# top.net
KiCad netlist of a schematic drawn in Altium Designer
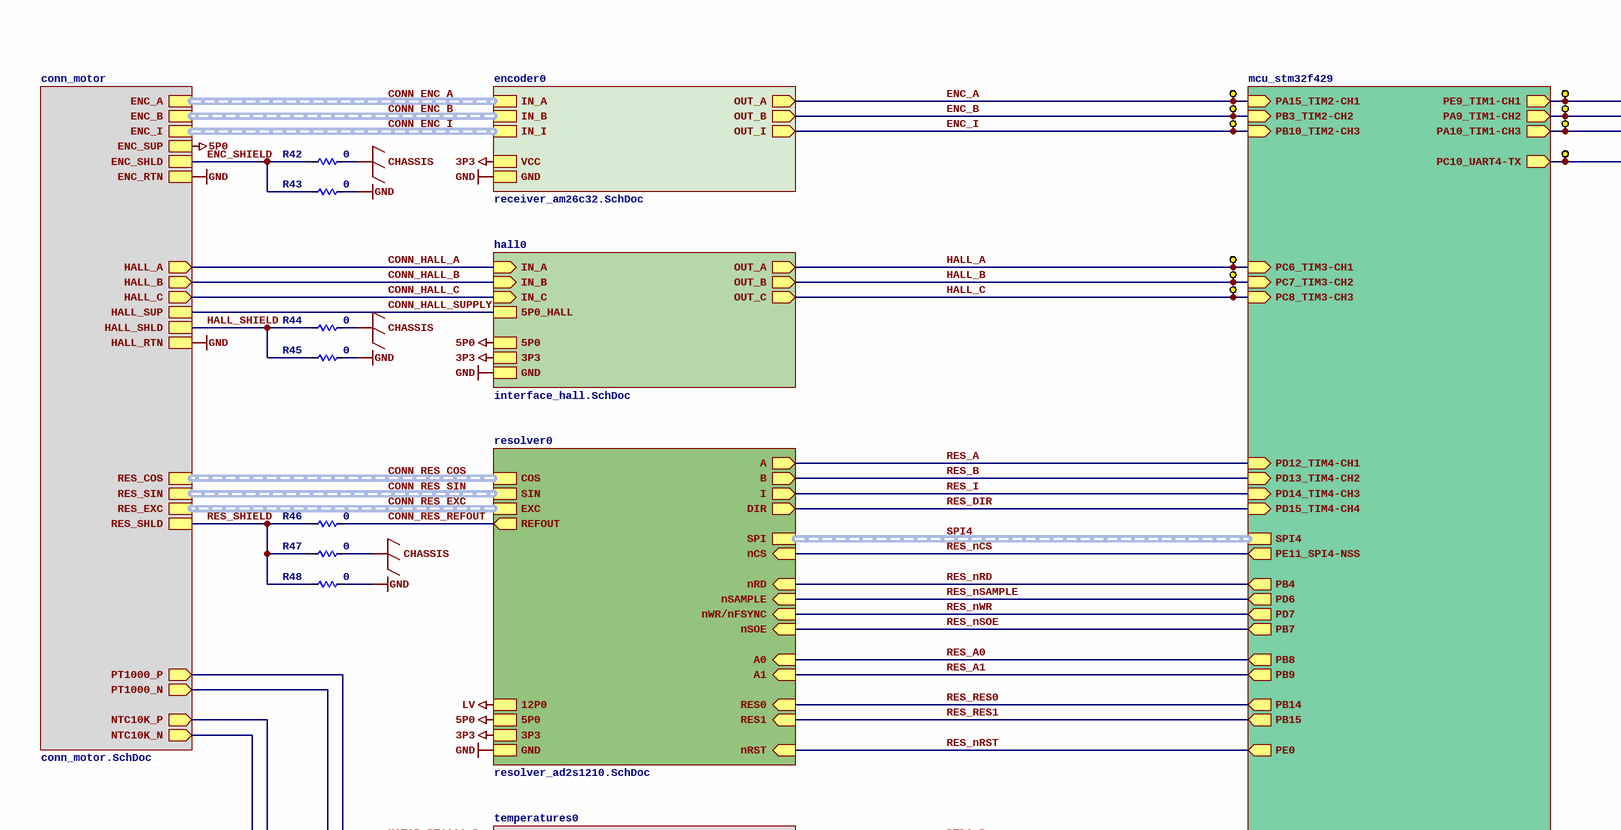
[diagram p0: top.SchDoc, top left]
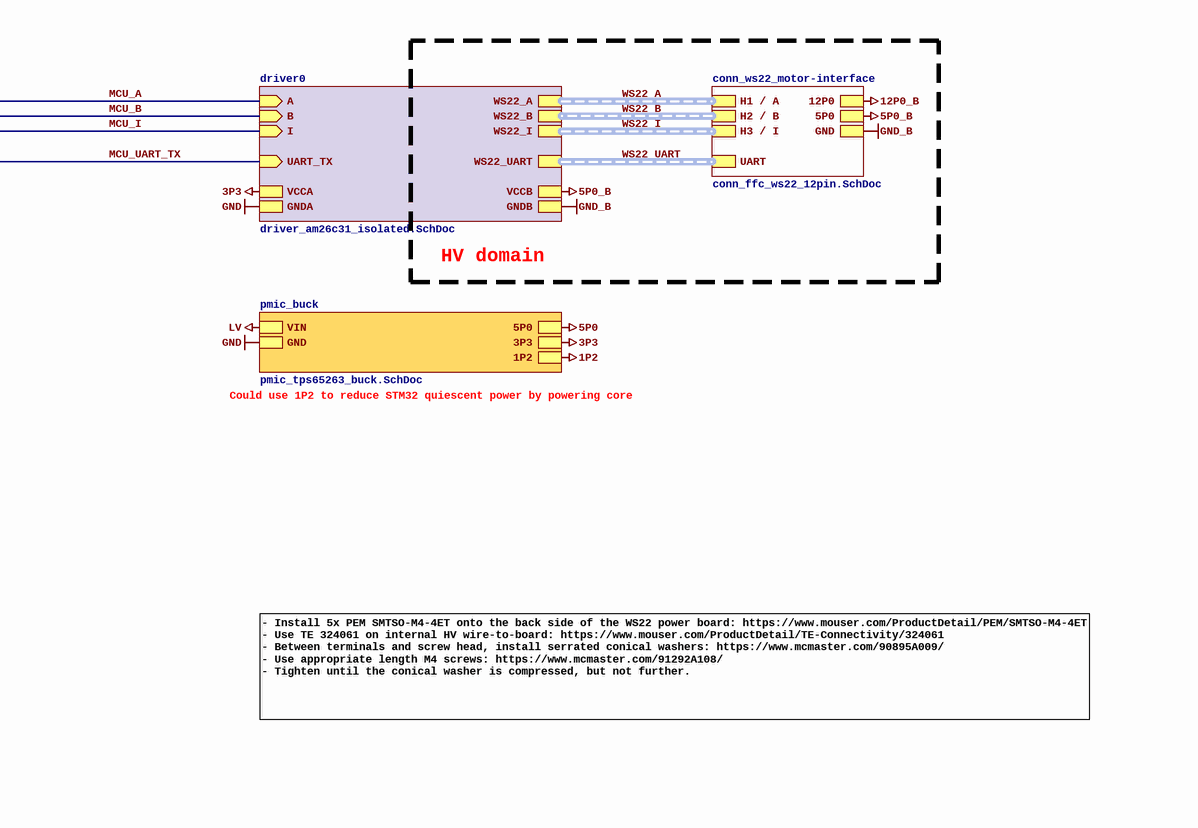
[diagram p1: top.SchDoc, top right]
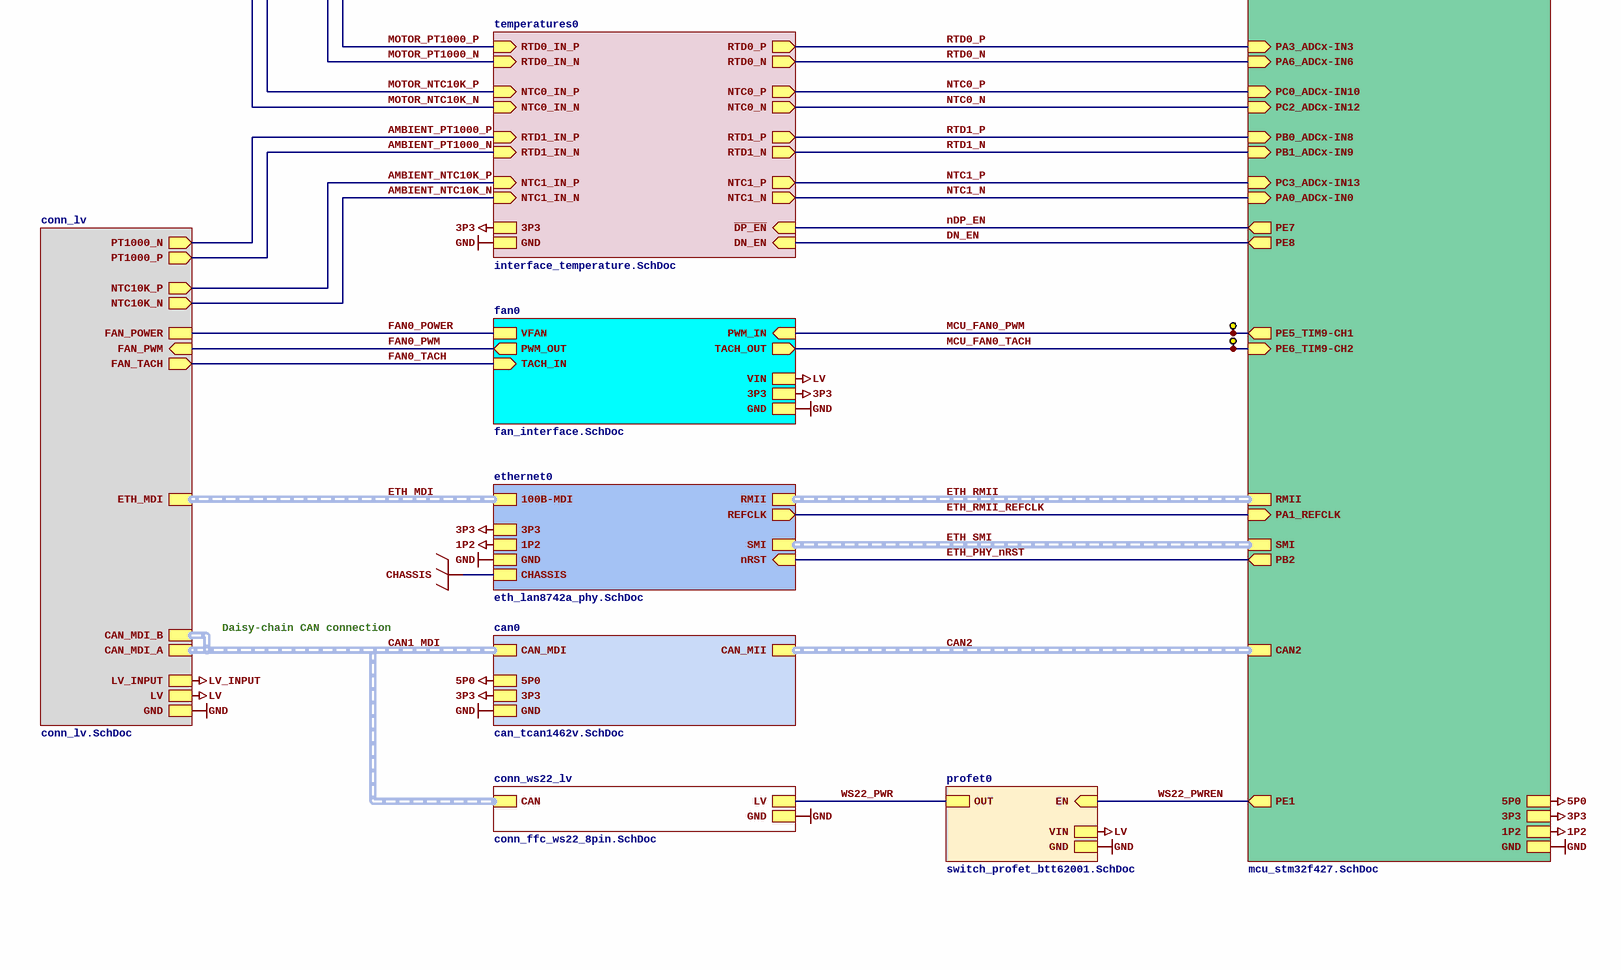
[diagram p2: top.SchDoc, bottom left]
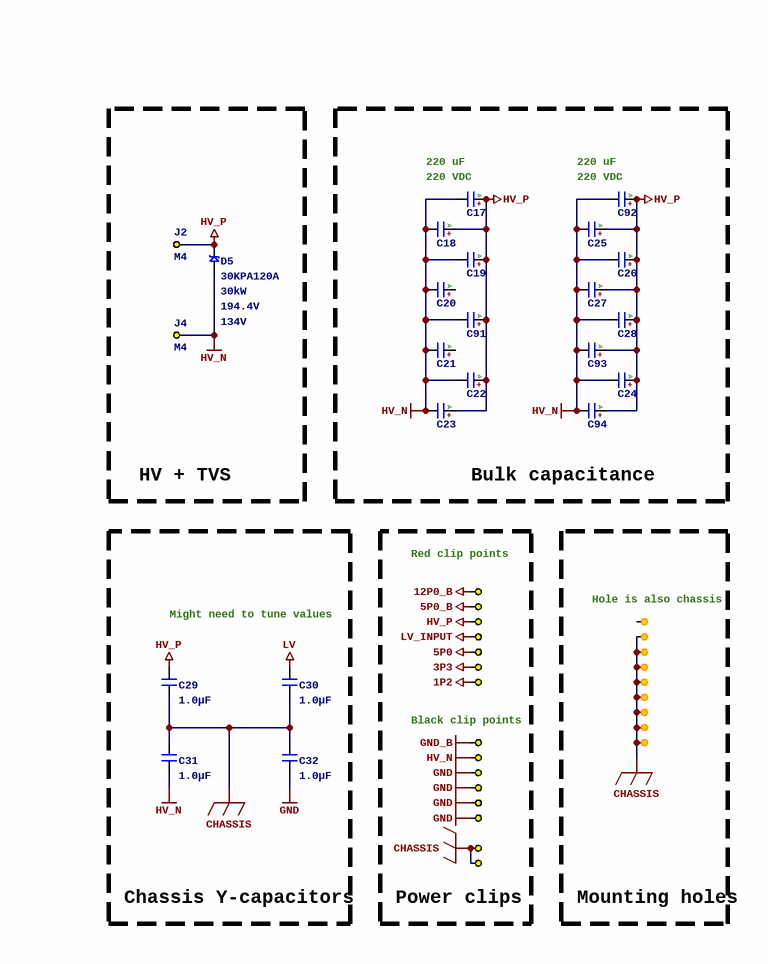
[diagram p3: top.SchDoc, bottom right]

(export (version "E")
  (design (tool "Eeschema 10.0.6"))
  (components
    (comp (ref "C17")
      (value "EKXJ221ELL221MM25S")
      (footprint "CAP_1600X2700X750")
      (fields (field (name "MANUFACTURER") "United Chemi-Con"))
      (libsource (lib "SSCP") (part "AUTO_CAP_ALUM_220UF_220V_EKXJ221ELL221MM25S"))
    )
    (comp (ref "C18")
      (value "EKXJ221ELL221MM25S")
      (footprint "CAP_1600X2700X750")
      (fields (field (name "MANUFACTURER") "United Chemi-Con"))
      (libsource (lib "SSCP") (part "AUTO_CAP_ALUM_220UF_220V_EKXJ221ELL221MM25S"))
    )
    (comp (ref "C19")
      (value "EKXJ221ELL221MM25S")
      (footprint "CAP_1600X2700X750")
      (fields (field (name "MANUFACTURER") "United Chemi-Con"))
      (libsource (lib "SSCP") (part "AUTO_CAP_ALUM_220UF_220V_EKXJ221ELL221MM25S"))
    )
    (comp (ref "C20")
      (value "EKXJ221ELL221MM25S")
      (footprint "CAP_1600X2700X750")
      (fields (field (name "MANUFACTURER") "United Chemi-Con"))
      (libsource (lib "SSCP") (part "AUTO_CAP_ALUM_220UF_220V_EKXJ221ELL221MM25S"))
    )
    (comp (ref "C21")
      (value "EKXJ221ELL221MM25S")
      (footprint "CAP_1600X2700X750")
      (fields (field (name "MANUFACTURER") "United Chemi-Con"))
      (libsource (lib "SSCP") (part "AUTO_CAP_ALUM_220UF_220V_EKXJ221ELL221MM25S"))
    )
    (comp (ref "C22")
      (value "EKXJ221ELL221MM25S")
      (footprint "CAP_1600X2700X750")
      (fields (field (name "MANUFACTURER") "United Chemi-Con"))
      (libsource (lib "SSCP") (part "AUTO_CAP_ALUM_220UF_220V_EKXJ221ELL221MM25S"))
    )
    (comp (ref "C23")
      (value "EKXJ221ELL221MM25S")
      (footprint "CAP_1600X2700X750")
      (fields (field (name "MANUFACTURER") "United Chemi-Con"))
      (libsource (lib "SSCP") (part "AUTO_CAP_ALUM_220UF_220V_EKXJ221ELL221MM25S"))
    )
    (comp (ref "C24")
      (value "EKXJ221ELL221MM25S")
      (footprint "CAP_1600X2700X750")
      (fields (field (name "MANUFACTURER") "United Chemi-Con"))
      (libsource (lib "SSCP") (part "AUTO_CAP_ALUM_220UF_220V_EKXJ221ELL221MM25S"))
    )
    (comp (ref "C25")
      (value "EKXJ221ELL221MM25S")
      (footprint "CAP_1600X2700X750")
      (fields (field (name "MANUFACTURER") "United Chemi-Con"))
      (libsource (lib "SSCP") (part "AUTO_CAP_ALUM_220UF_220V_EKXJ221ELL221MM25S"))
    )
    (comp (ref "C26")
      (value "EKXJ221ELL221MM25S")
      (footprint "CAP_1600X2700X750")
      (fields (field (name "MANUFACTURER") "United Chemi-Con"))
      (libsource (lib "SSCP") (part "AUTO_CAP_ALUM_220UF_220V_EKXJ221ELL221MM25S"))
    )
    (comp (ref "C27")
      (value "EKXJ221ELL221MM25S")
      (footprint "CAP_1600X2700X750")
      (fields (field (name "MANUFACTURER") "United Chemi-Con"))
      (libsource (lib "SSCP") (part "AUTO_CAP_ALUM_220UF_220V_EKXJ221ELL221MM25S"))
    )
    (comp (ref "C28")
      (value "EKXJ221ELL221MM25S")
      (footprint "CAP_1600X2700X750")
      (fields (field (name "MANUFACTURER") "United Chemi-Con"))
      (libsource (lib "SSCP") (part "AUTO_CAP_ALUM_220UF_220V_EKXJ221ELL221MM25S"))
    )
    (comp (ref "C29")
      (value "MPB105J2WD4KN1580S")
      (footprint "KNSCHA-CAP-MPB-S")
      (description "CAP FILM 1UF 5% 450V RADIAL")
      (fields (field (name "MANUFACTURER") "KNSCHA") (field (name "CAPACITANCE") "1.0µF"))
      (libsource (lib "SSCP") (part "CAP_FILM_1UF_450V"))
    )
    (comp (ref "C30")
      (value "MPB105J2WD4KN1580S")
      (footprint "KNSCHA-CAP-MPB-S")
      (description "CAP FILM 1UF 5% 450V RADIAL")
      (fields (field (name "MANUFACTURER") "KNSCHA") (field (name "CAPACITANCE") "1.0µF"))
      (libsource (lib "SSCP") (part "CAP_FILM_1UF_450V"))
    )
    (comp (ref "C31")
      (value "MPB105J2WD4KN1580S")
      (footprint "KNSCHA-CAP-MPB-S")
      (description "CAP FILM 1UF 5% 450V RADIAL")
      (fields (field (name "MANUFACTURER") "KNSCHA") (field (name "CAPACITANCE") "1.0µF"))
      (libsource (lib "SSCP") (part "CAP_FILM_1UF_450V"))
    )
    (comp (ref "C32")
      (value "MPB105J2WD4KN1580S")
      (footprint "KNSCHA-CAP-MPB-S")
      (description "CAP FILM 1UF 5% 450V RADIAL")
      (fields (field (name "MANUFACTURER") "KNSCHA") (field (name "CAPACITANCE") "1.0µF"))
      (libsource (lib "SSCP") (part "CAP_FILM_1UF_450V"))
    )
    (comp (ref "C91")
      (value "EKXJ221ELL221MM25S")
      (footprint "CAP_1600X2700X750")
      (fields (field (name "MANUFACTURER") "United Chemi-Con"))
      (libsource (lib "SSCP") (part "AUTO_CAP_ALUM_220UF_220V_EKXJ221ELL221MM25S"))
    )
    (comp (ref "C92")
      (value "EKXJ221ELL221MM25S")
      (footprint "CAP_1600X2700X750")
      (fields (field (name "MANUFACTURER") "United Chemi-Con"))
      (libsource (lib "SSCP") (part "AUTO_CAP_ALUM_220UF_220V_EKXJ221ELL221MM25S"))
    )
    (comp (ref "C93")
      (value "EKXJ221ELL221MM25S")
      (footprint "CAP_1600X2700X750")
      (fields (field (name "MANUFACTURER") "United Chemi-Con"))
      (libsource (lib "SSCP") (part "AUTO_CAP_ALUM_220UF_220V_EKXJ221ELL221MM25S"))
    )
    (comp (ref "C94")
      (value "EKXJ221ELL221MM25S")
      (footprint "CAP_1600X2700X750")
      (fields (field (name "MANUFACTURER") "United Chemi-Con"))
      (libsource (lib "SSCP") (part "AUTO_CAP_ALUM_220UF_220V_EKXJ221ELL221MM25S"))
    )
    (comp (ref "D5")
      (value "30KPA120A")
      (footprint "P600")
      (description "Trans Voltage Suppressor Diode, 30000W, 120V V(RWM), Unidirectional, 1 Element, Silicon")
      (fields
        (field (name "MANUFACTURER") "Littelfuse")
        (field (name "NON-REP PEAK REV POWER DIS-MAX") "30kW")
        (field (name "CLAMPING VOLTAGE-MAX") "194.4V")
        (field (name "MIN BREAKDOWN VOLTAGE") "134V")
      )
      (libsource (lib "SSCP") (part "TVS_UNI_30KPA120A"))
    )
    (comp (ref "J2")
      (value "~")
      (footprint "WURTH_TERM_7461086")
      (description "POWER ELEMENT BUSH M4 12PIN")
      (fields
        (field (name "MANUFACTURER") "Wurth Electronics")
        (field (name "MANUFACTURER PART NUMBER") "7461086")
        (field (name "THREAD SIZE") "M4")
      )
      (libsource (lib "SSCP") (part "CONN_WURTH_7461086"))
    )
    (comp (ref "J4")
      (value "~")
      (footprint "WURTH_TERM_7461086")
      (description "POWER ELEMENT BUSH M4 12PIN")
      (fields
        (field (name "MANUFACTURER") "Wurth Electronics")
        (field (name "MANUFACTURER PART NUMBER") "7461086")
        (field (name "THREAD SIZE") "M4")
      )
      (libsource (lib "SSCP") (part "CONN_WURTH_7461086"))
    )
    (comp (ref "MH1") (value "HOLE_M3") (footprint "HOLE_M3") (libsource (lib "SSCP") (part "HOLE_M3")))
    (comp (ref "MH2") (value "HOLE_M3") (footprint "HOLE_M3") (libsource (lib "SSCP") (part "HOLE_M3")))
    (comp (ref "MH3") (value "HOLE_M3") (footprint "HOLE_M3") (libsource (lib "SSCP") (part "HOLE_M3")))
    (comp (ref "MH4") (value "HOLE_M3") (footprint "HOLE_M3") (libsource (lib "SSCP") (part "HOLE_M3")))
    (comp (ref "MH5") (value "HOLE_M3") (footprint "HOLE_M3") (libsource (lib "SSCP") (part "HOLE_M3")))
    (comp (ref "MH6") (value "HOLE_M3") (footprint "HOLE_M3") (libsource (lib "SSCP") (part "HOLE_M3")))
    (comp (ref "MH7") (value "HOLE_M3") (footprint "HOLE_M3") (libsource (lib "SSCP") (part "HOLE_M3")))
    (comp (ref "MH8") (value "HOLE_M3") (footprint "HOLE_M3") (libsource (lib "SSCP") (part "HOLE_M3")))
    (comp (ref "MH9") (value "HOLE_M3") (footprint "HOLE_M3") (libsource (lib "SSCP") (part "HOLE_M3")))
    (comp (ref "R42")
      (value "ERJ-2GE0R00X")
      (footprint "R0402_0.40MM")
      (description "RES SMD 0 OHM JUMPER 1/10W 0402")
      (fields
        (field (name "RESISTANCE") "0")
        (field (name "TOLERANCE") "Jumper")
        (field (name "MANUFACTURER") "Panasonic Electronic Components")
      )
      (libsource (lib "sscp") (part "__template_resistor"))
    )
    (comp (ref "R43")
      (value "ERJ-2GE0R00X")
      (footprint "R0402_0.40MM")
      (description "RES SMD 0 OHM JUMPER 1/10W 0402")
      (fields
        (field (name "RESISTANCE") "0")
        (field (name "TOLERANCE") "Jumper")
        (field (name "MANUFACTURER") "Panasonic Electronic Components")
      )
      (libsource (lib "sscp") (part "__template_resistor"))
    )
    (comp (ref "R44")
      (value "ERJ-2GE0R00X")
      (footprint "R0402_0.40MM")
      (description "RES SMD 0 OHM JUMPER 1/10W 0402")
      (fields
        (field (name "RESISTANCE") "0")
        (field (name "TOLERANCE") "Jumper")
        (field (name "MANUFACTURER") "Panasonic Electronic Components")
      )
      (libsource (lib "sscp") (part "__template_resistor"))
    )
    (comp (ref "R45")
      (value "ERJ-2GE0R00X")
      (footprint "R0402_0.40MM")
      (description "RES SMD 0 OHM JUMPER 1/10W 0402")
      (fields
        (field (name "RESISTANCE") "0")
        (field (name "TOLERANCE") "Jumper")
        (field (name "MANUFACTURER") "Panasonic Electronic Components")
      )
      (libsource (lib "sscp") (part "__template_resistor"))
    )
    (comp (ref "R46")
      (value "ERJ-2GE0R00X")
      (footprint "R0402_0.40MM")
      (description "RES SMD 0 OHM JUMPER 1/10W 0402")
      (fields
        (field (name "RESISTANCE") "0")
        (field (name "TOLERANCE") "Jumper")
        (field (name "MANUFACTURER") "Panasonic Electronic Components")
      )
      (libsource (lib "sscp") (part "__template_resistor"))
    )
    (comp (ref "R47")
      (value "ERJ-2GE0R00X")
      (footprint "R0402_0.40MM")
      (description "RES SMD 0 OHM JUMPER 1/10W 0402")
      (fields
        (field (name "RESISTANCE") "0")
        (field (name "TOLERANCE") "Jumper")
        (field (name "MANUFACTURER") "Panasonic Electronic Components")
      )
      (libsource (lib "sscp") (part "__template_resistor"))
    )
    (comp (ref "R48")
      (value "ERJ-2GE0R00X")
      (footprint "R0402_0.40MM")
      (description "RES SMD 0 OHM JUMPER 1/10W 0402")
      (fields
        (field (name "RESISTANCE") "0")
        (field (name "TOLERANCE") "Jumper")
        (field (name "MANUFACTURER") "Panasonic Electronic Components")
      )
      (libsource (lib "sscp") (part "__template_resistor"))
    )
    (comp (ref "TP8")
      (value "~")
      (footprint "TP_GRABBY")
      (description "EMBEDDED TEST POINT FOR SALEAE TEST CLIPS")
      (libsource (lib "SSCP") (part "TEST_GRABBER"))
    )
    (comp (ref "TP9")
      (value "~")
      (footprint "TP_GRABBY")
      (description "EMBEDDED TEST POINT FOR SALEAE TEST CLIPS")
      (libsource (lib "SSCP") (part "TEST_GRABBER"))
    )
    (comp (ref "TP10")
      (value "~")
      (footprint "TP_GRABBY")
      (description "EMBEDDED TEST POINT FOR SALEAE TEST CLIPS")
      (libsource (lib "SSCP") (part "TEST_GRABBER"))
    )
    (comp (ref "TP11")
      (value "~")
      (footprint "TP_GRABBY")
      (description "EMBEDDED TEST POINT FOR SALEAE TEST CLIPS")
      (libsource (lib "SSCP") (part "TEST_GRABBER"))
    )
    (comp (ref "TP12")
      (value "~")
      (footprint "TP_GRABBY")
      (description "EMBEDDED TEST POINT FOR SALEAE TEST CLIPS")
      (libsource (lib "SSCP") (part "TEST_GRABBER"))
    )
    (comp (ref "TP13")
      (value "~")
      (footprint "TP_GRABBY")
      (description "EMBEDDED TEST POINT FOR SALEAE TEST CLIPS")
      (libsource (lib "SSCP") (part "TEST_GRABBER"))
    )
    (comp (ref "TP14")
      (value "~")
      (footprint "TP_GRABBY")
      (description "EMBEDDED TEST POINT FOR SALEAE TEST CLIPS")
      (libsource (lib "SSCP") (part "TEST_GRABBER"))
    )
    (comp (ref "TP15")
      (value "~")
      (footprint "TP_GRABBY")
      (description "EMBEDDED TEST POINT FOR SALEAE TEST CLIPS")
      (libsource (lib "SSCP") (part "TEST_GRABBER"))
    )
    (comp (ref "TP16")
      (value "~")
      (footprint "TP_GRABBY")
      (description "EMBEDDED TEST POINT FOR SALEAE TEST CLIPS")
      (libsource (lib "SSCP") (part "TEST_GRABBER"))
    )
    (comp (ref "TP17")
      (value "~")
      (footprint "TP_GRABBY")
      (description "EMBEDDED TEST POINT FOR SALEAE TEST CLIPS")
      (libsource (lib "SSCP") (part "TEST_GRABBER"))
    )
    (comp (ref "TP32")
      (value "~")
      (footprint "TP_GRABBY")
      (description "EMBEDDED TEST POINT FOR SALEAE TEST CLIPS")
      (libsource (lib "SSCP") (part "TEST_GRABBER"))
    )
    (comp (ref "TP33")
      (value "~")
      (footprint "TP_GRABBY")
      (description "EMBEDDED TEST POINT FOR SALEAE TEST CLIPS")
      (libsource (lib "SSCP") (part "TEST_GRABBER"))
    )
    (comp (ref "TP37")
      (value "RH-5000")
      (footprint "TP_RH-5000")
      (description "THT red clip turret")
      (fields (field (name "MANUFACTURER") "ronghe"))
      (libsource (lib "sscp") (part "__template_testpoint"))
    )
    (comp (ref "TP38")
      (value "RH-5000")
      (footprint "TP_RH-5000")
      (description "THT red clip turret")
      (fields (field (name "MANUFACTURER") "ronghe"))
      (libsource (lib "sscp") (part "__template_testpoint"))
    )
    (comp (ref "TP39")
      (value "RH-5000")
      (footprint "TP_RH-5000")
      (description "THT red clip turret")
      (fields (field (name "MANUFACTURER") "ronghe"))
      (libsource (lib "sscp") (part "__template_testpoint"))
    )
    (comp (ref "TP41")
      (value "RH-5000")
      (footprint "TP_RH-5000")
      (description "THT red clip turret")
      (fields (field (name "MANUFACTURER") "ronghe"))
      (libsource (lib "sscp") (part "__template_testpoint"))
    )
    (comp (ref "TP42")
      (value "RH-5000")
      (footprint "TP_RH-5000")
      (description "THT red clip turret")
      (fields (field (name "MANUFACTURER") "ronghe"))
      (libsource (lib "sscp") (part "__template_testpoint"))
    )
    (comp (ref "TP43")
      (value "RH-5000")
      (footprint "TP_RH-5000")
      (description "THT red clip turret")
      (fields (field (name "MANUFACTURER") "ronghe"))
      (libsource (lib "sscp") (part "__template_testpoint"))
    )
    (comp (ref "TP44")
      (value "RH-5000")
      (footprint "TP_RH-5000")
      (description "THT red clip turret")
      (fields (field (name "MANUFACTURER") "ronghe"))
      (libsource (lib "sscp") (part "__template_testpoint"))
    )
    (comp (ref "TP45")
      (value "RH-5001")
      (footprint "TP_RH-5001")
      (description "THT black clip turret")
      (fields (field (name "MANUFACTURER") "ronghe"))
      (libsource (lib "sscp") (part "__template_testpoint"))
    )
    (comp (ref "TP47")
      (value "RH-5001")
      (footprint "TP_RH-5001")
      (description "THT black clip turret")
      (fields (field (name "MANUFACTURER") "ronghe"))
      (libsource (lib "sscp") (part "__template_testpoint"))
    )
    (comp (ref "TP48")
      (value "RH-5001")
      (footprint "TP_RH-5001")
      (description "THT black clip turret")
      (fields (field (name "MANUFACTURER") "ronghe"))
      (libsource (lib "sscp") (part "__template_testpoint"))
    )
    (comp (ref "TP49")
      (value "RH-5001")
      (footprint "TP_RH-5001")
      (description "THT black clip turret")
      (fields (field (name "MANUFACTURER") "ronghe"))
      (libsource (lib "sscp") (part "__template_testpoint"))
    )
    (comp (ref "TP50")
      (value "RH-5001")
      (footprint "TP_RH-5001")
      (description "THT black clip turret")
      (fields (field (name "MANUFACTURER") "ronghe"))
      (libsource (lib "sscp") (part "__template_testpoint"))
    )
    (comp (ref "TP51")
      (value "RH-5001")
      (footprint "TP_RH-5001")
      (description "THT black clip turret")
      (fields (field (name "MANUFACTURER") "ronghe"))
      (libsource (lib "sscp") (part "__template_testpoint"))
    )
    (comp (ref "TP52")
      (value "RH-5001")
      (footprint "TP_RH-5001")
      (description "THT black clip turret")
      (fields (field (name "MANUFACTURER") "ronghe"))
      (libsource (lib "sscp") (part "__template_testpoint"))
    )
    (comp (ref "TP53")
      (value "RH-5001")
      (footprint "TP_RH-5001")
      (description "THT black clip turret")
      (fields (field (name "MANUFACTURER") "ronghe"))
      (libsource (lib "sscp") (part "__template_testpoint"))
    )
  )
  (nets
    (net (code "25") (name "/CONN_RES_REFOUT") (class "Default")
      (node (ref "R46") (pin "1") (pintype "passive"))
    )
    (net (code "27") (name "/ENC_A") (class "Default") (node (ref "TP8") (pin "1") (pintype "passive")))
    (net (code "28") (name "/ENC_B") (class "Default") (node (ref "TP10") (pin "1") (pintype "passive")))
    (net (code "29") (name "/ENC_I") (class "Default") (node (ref "TP12") (pin "1") (pintype "passive")))
    (net (code "30") (name "/ENC_SHIELD") (class "Default")
      (node (ref "R42") (pin "2") (pintype "passive"))
      (node (ref "R43") (pin "2") (pintype "passive"))
    )
    (net (code "36") (name "/HALL_A") (class "Default") (node (ref "TP15") (pin "1") (pintype "passive")))
    (net (code "37") (name "/HALL_B") (class "Default") (node (ref "TP16") (pin "1") (pintype "passive")))
    (net (code "38") (name "/HALL_C") (class "Default") (node (ref "TP17") (pin "1") (pintype "passive")))
    (net (code "39") (name "/HALL_SHIELD") (class "Default")
      (node (ref "R44") (pin "2") (pintype "passive"))
      (node (ref "R45") (pin "2") (pintype "passive"))
    )
    (net (code "40") (name "/MCU_A") (class "Default") (node (ref "TP9") (pin "1") (pintype "passive")))
    (net (code "41") (name "/MCU_B") (class "Default") (node (ref "TP11") (pin "1") (pintype "passive")))
    (net (code "42") (name "/MCU_FAN0_PWM") (class "Default")
      (node (ref "TP32") (pin "1") (pintype "passive"))
    )
    (net (code "43") (name "/MCU_FAN0_TACH") (class "Default")
      (node (ref "TP33") (pin "1") (pintype "passive"))
    )
    (net (code "44") (name "/MCU_I") (class "Default") (node (ref "TP13") (pin "1") (pintype "passive")))
    (net (code "45") (name "/MCU_UART_TX") (class "Default")
      (node (ref "TP14") (pin "1") (pintype "passive"))
    )
    (net (code "62") (name "/RES_SHIELD") (class "Default")
      (node (ref "R46") (pin "2") (pintype "passive"))
      (node (ref "R47") (pin "2") (pintype "passive"))
      (node (ref "R48") (pin "2") (pintype "passive"))
    )
    (net (code "92") (name "1P2") (class "Default") (node (ref "TP44") (pin "1") (pintype "passive")))
    (net (code "93") (name "3P3") (class "Default") (node (ref "TP43") (pin "1") (pintype "passive")))
    (net (code "94") (name "5P0") (class "Default") (node (ref "TP42") (pin "1") (pintype "passive")))
    (net (code "95") (name "5P0_B") (class "Default") (node (ref "TP38") (pin "1") (pintype "passive")))
    (net (code "96") (name "12P0_B") (class "Default") (node (ref "TP37") (pin "1") (pintype "passive")))
    (net (code "97") (name "CHASSIS") (class "Default")
      (node (ref "C29") (pin "2") (pintype "passive"))
      (node (ref "C30") (pin "2") (pintype "passive"))
      (node (ref "C31") (pin "1") (pintype "passive"))
      (node (ref "C32") (pin "1") (pintype "passive"))
      (node (ref "MH1") (pin "0") (pintype "passive"))
      (node (ref "MH2") (pin "0") (pintype "passive"))
      (node (ref "MH3") (pin "0") (pintype "passive"))
      (node (ref "MH4") (pin "0") (pintype "passive"))
      (node (ref "MH5") (pin "0") (pintype "passive"))
      (node (ref "MH6") (pin "0") (pintype "passive"))
      (node (ref "MH7") (pin "0") (pintype "passive"))
      (node (ref "MH8") (pin "0") (pintype "passive"))
      (node (ref "R42") (pin "1") (pintype "passive"))
      (node (ref "R44") (pin "1") (pintype "passive"))
      (node (ref "R47") (pin "1") (pintype "passive"))
      (node (ref "TP52") (pin "1") (pintype "passive"))
      (node (ref "TP53") (pin "1") (pintype "passive"))
    )
    (net (code "98") (name "GND") (class "Default")
      (node (ref "C32") (pin "2") (pintype "passive"))
      (node (ref "R43") (pin "1") (pintype "passive"))
      (node (ref "R45") (pin "1") (pintype "passive"))
      (node (ref "R48") (pin "1") (pintype "passive"))
      (node (ref "TP48") (pin "1") (pintype "passive"))
      (node (ref "TP49") (pin "1") (pintype "passive"))
      (node (ref "TP50") (pin "1") (pintype "passive"))
      (node (ref "TP51") (pin "1") (pintype "passive"))
    )
    (net (code "99") (name "GND_B") (class "Default") (node (ref "TP45") (pin "1") (pintype "passive")))
    (net (code "100") (name "HV_N") (class "Default")
      (node (ref "C17") (pin "2") (pintype "passive"))
      (node (ref "C18") (pin "2") (pintype "passive"))
      (node (ref "C19") (pin "2") (pintype "passive"))
      (node (ref "C20") (pin "2") (pintype "passive"))
      (node (ref "C21") (pin "2") (pintype "passive"))
      (node (ref "C22") (pin "2") (pintype "passive"))
      (node (ref "C23") (pin "2") (pintype "passive"))
      (node (ref "C24") (pin "2") (pintype "passive"))
      (node (ref "C25") (pin "2") (pintype "passive"))
      (node (ref "C26") (pin "2") (pintype "passive"))
      (node (ref "C27") (pin "2") (pintype "passive"))
      (node (ref "C28") (pin "2") (pintype "passive"))
      (node (ref "C31") (pin "2") (pintype "passive"))
      (node (ref "C91") (pin "2") (pintype "passive"))
      (node (ref "C92") (pin "2") (pintype "passive"))
      (node (ref "C93") (pin "2") (pintype "passive"))
      (node (ref "C94") (pin "2") (pintype "passive"))
      (node (ref "D5") (pin "1") (pintype "passive"))
      (node (ref "J4") (pin "0") (pintype "passive"))
      (node (ref "TP47") (pin "1") (pintype "passive"))
    )
    (net (code "101") (name "HV_P") (class "Default")
      (node (ref "C17") (pin "1") (pintype "passive"))
      (node (ref "C18") (pin "1") (pintype "passive"))
      (node (ref "C19") (pin "1") (pintype "passive"))
      (node (ref "C22") (pin "1") (pintype "passive"))
      (node (ref "C23") (pin "1") (pintype "passive"))
      (node (ref "C24") (pin "1") (pintype "passive"))
      (node (ref "C25") (pin "1") (pintype "passive"))
      (node (ref "C26") (pin "1") (pintype "passive"))
      (node (ref "C27") (pin "1") (pintype "passive"))
      (node (ref "C28") (pin "1") (pintype "passive"))
      (node (ref "C29") (pin "1") (pintype "passive"))
      (node (ref "C91") (pin "1") (pintype "passive"))
      (node (ref "C92") (pin "1") (pintype "passive"))
      (node (ref "C93") (pin "1") (pintype "passive"))
      (node (ref "C94") (pin "1") (pintype "passive"))
      (node (ref "D5") (pin "2") (pintype "passive"))
      (node (ref "J2") (pin "0") (pintype "passive"))
      (node (ref "TP39") (pin "1") (pintype "passive"))
    )
    (net (code "102") (name "LV") (class "Default") (node (ref "C30") (pin "1") (pintype "passive")))
    (net (code "103") (name "LV_INPUT") (class "Default") (node (ref "TP41") (pin "1") (pintype "passive")))
    (net (code "104") (name "unconnected-(C20-Pad1)") (class "Default")
      (node (ref "C20") (pin "1") (pintype "passive"))
    )
    (net (code "105") (name "unconnected-(C21-Pad1)") (class "Default")
      (node (ref "C21") (pin "1") (pintype "passive"))
    )
    (net (code "106") (name "unconnected-(MH9-Pad0)") (class "Default")
      (node (ref "MH9") (pin "0") (pintype "passive"))
    )
  )
)
